# TrackerMini_V2.net
KiCad netlist of a schematic drawn in EAGLE
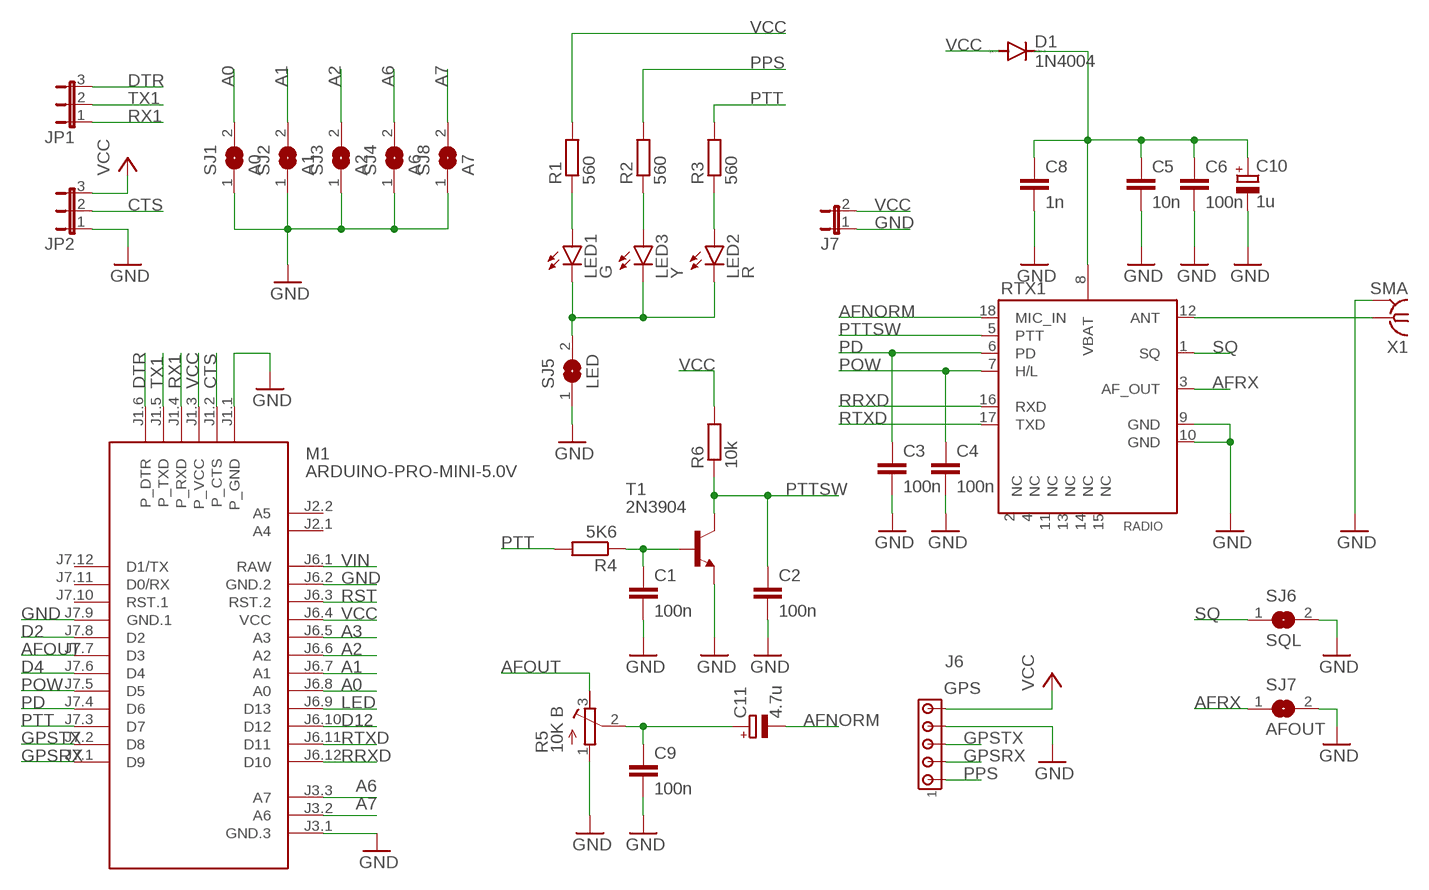
[diagram p0: schematic, sheet 1]

(export (version "E")
  (design (tool "Eeschema 10.0.6"))
  (components
    (comp (ref "C1")
      (value "100n")
      (footprint "eagle-import:C025-025X050")
      (libsource (lib "eagle-import") (part "C-EU025-025X050"))
    )
    (comp (ref "C2")
      (value "100n")
      (footprint "eagle-import:C025-025X050")
      (libsource (lib "eagle-import") (part "C-EU025-025X050"))
    )
    (comp (ref "C3")
      (value "100n")
      (footprint "eagle-import:C025-025X050")
      (libsource (lib "eagle-import") (part "C-EU025-025X050"))
    )
    (comp (ref "C4")
      (value "100n")
      (footprint "eagle-import:C025-025X050")
      (libsource (lib "eagle-import") (part "C-EU025-025X050"))
    )
    (comp (ref "C5")
      (value "10n")
      (footprint "eagle-import:C025-025X050")
      (libsource (lib "eagle-import") (part "C-EU025-025X050"))
    )
    (comp (ref "C6")
      (value "100n")
      (footprint "eagle-import:C025-025X050")
      (libsource (lib "eagle-import") (part "C-EU025-025X050"))
    )
    (comp (ref "C8")
      (value "1n")
      (footprint "eagle-import:C025-025X050")
      (libsource (lib "eagle-import") (part "C-EU025-025X050"))
    )
    (comp (ref "C9")
      (value "100n")
      (footprint "eagle-import:C025-025X050")
      (libsource (lib "eagle-import") (part "C-EU025-025X050"))
    )
    (comp (ref "C10")
      (value "1u")
      (footprint "eagle-import:E2-5")
      (libsource (lib "eagle-import") (part "CPOL-EUE2-5"))
    )
    (comp (ref "C11")
      (value "4.7u")
      (footprint "eagle-import:E2-5")
      (libsource (lib "eagle-import") (part "CPOL-EUE2-5"))
    )
    (comp (ref "D1")
      (value "1N4004")
      (footprint "eagle-import:DO41-10")
      (libsource (lib "eagle-import") (part "1N4004"))
    )
    (comp (ref "J6")
      (value "GPS")
      (footprint "eagle-import:10X05MTA")
      (libsource (lib "eagle-import") (part "MTA05-100"))
    )
    (comp (ref "J7")
      (value "JP1E")
      (footprint "eagle-import:JP1")
      (libsource (lib "eagle-import") (part "JP1E"))
    )
    (comp (ref "JP1")
      (value "JP2E")
      (footprint "eagle-import:JP2")
      (libsource (lib "eagle-import") (part "JP2E"))
    )
    (comp (ref "JP2")
      (value "JP2E")
      (footprint "eagle-import:JP2")
      (libsource (lib "eagle-import") (part "JP2E"))
    )
    (comp (ref "LED1")
      (value "G")
      (footprint "eagle-import:LED3MM")
      (fields (field (name "MF") "VISHAY SEMICONDUCTOR"))
      (libsource (lib "eagle-import") (part "TLLG4400"))
    )
    (comp (ref "LED2")
      (value "R")
      (footprint "eagle-import:LED3MM")
      (fields (field (name "MF") "VISHAY SEMICONDUCTOR"))
      (libsource (lib "eagle-import") (part "TLLR4400"))
    )
    (comp (ref "LED3")
      (value "Y")
      (footprint "eagle-import:LED3MM")
      (fields (field (name "MF") "VISHAY SEMICONDUCTOR"))
      (libsource (lib "eagle-import") (part "TLLY4400"))
    )
    (comp (ref "M1")
      (value "ARDUINO-PRO-MINI-5.0V")
      (footprint "eagle-import:ARDUINO-PRO-MINI")
      (libsource (lib "eagle-import") (part "ARDUINO-PRO-MINI-5.0V"))
    )
    (comp (ref "R1")
      (value "560")
      (footprint "eagle-import:0204_7")
      (libsource (lib "eagle-import") (part "R-EU_0204/7"))
    )
    (comp (ref "R2")
      (value "560")
      (footprint "eagle-import:0204_7")
      (libsource (lib "eagle-import") (part "R-EU_0204/7"))
    )
    (comp (ref "R3")
      (value "560")
      (footprint "eagle-import:0204_7")
      (libsource (lib "eagle-import") (part "R-EU_0204/7"))
    )
    (comp (ref "R4")
      (value "5K6")
      (footprint "eagle-import:0204_7")
      (libsource (lib "eagle-import") (part "R-EU_0204/7"))
    )
    (comp (ref "R5")
      (value "10K B")
      (footprint "eagle-import:RTRIM64W")
      (libsource (lib "eagle-import") (part "R-TRIMM64W"))
    )
    (comp (ref "R6")
      (value "10k")
      (footprint "eagle-import:0204_7")
      (libsource (lib "eagle-import") (part "R-EU_0204/7"))
    )
    (comp (ref "RTX1")
      (value "RADIO")
      (footprint "eagle-import:DRA818A")
      (libsource (lib "eagle-import") (part "DRA818A"))
    )
    (comp (ref "SJ1") (value "A0") (footprint "eagle-import:SJ") (libsource (lib "eagle-import") (part "SJ")))
    (comp (ref "SJ2") (value "A1") (footprint "eagle-import:SJ") (libsource (lib "eagle-import") (part "SJ")))
    (comp (ref "SJ3") (value "A2") (footprint "eagle-import:SJ") (libsource (lib "eagle-import") (part "SJ")))
    (comp (ref "SJ4") (value "A6") (footprint "eagle-import:SJ") (libsource (lib "eagle-import") (part "SJ")))
    (comp (ref "SJ5")
      (value "LED")
      (footprint "eagle-import:SJ")
      (libsource (lib "eagle-import") (part "SJ"))
    )
    (comp (ref "SJ6")
      (value "SQL")
      (footprint "eagle-import:SJW")
      (libsource (lib "eagle-import") (part "SJW"))
    )
    (comp (ref "SJ7")
      (value "AFOUT")
      (footprint "eagle-import:SJW")
      (libsource (lib "eagle-import") (part "SJW"))
    )
    (comp (ref "SJ8") (value "A7") (footprint "eagle-import:SJ") (libsource (lib "eagle-import") (part "SJ")))
    (comp (ref "T1")
      (value "2N3904")
      (footprint "eagle-import:TO92")
      (libsource (lib "eagle-import") (part "2N3904"))
    )
    (comp (ref "X1")
      (value "SMA")
      (footprint "eagle-import:J502-ND-142-0701-801_806")
      (fields (field (name "MF") "JOHNSON COMPONENTS") (field (name "MPN") "142-0701-801"))
      (libsource (lib "eagle-import") (part "SMA-142-0701-801/806"))
    )
  )
  (nets
    (net (code "1") (name "/A0") (class "Default")
      (node (ref "M1") (pin "J6.8") (pinfunction "A0_J6.8") (pintype "bidirectional"))
      (node (ref "SJ1") (pin "2") (pinfunction "2_2") (pintype "passive"))
    )
    (net (code "2") (name "/A1") (class "Default")
      (node (ref "M1") (pin "J6.7") (pinfunction "A1_J6.7") (pintype "bidirectional"))
      (node (ref "SJ2") (pin "2") (pinfunction "2_2") (pintype "passive"))
    )
    (net (code "3") (name "/A2") (class "Default")
      (node (ref "M1") (pin "J6.6") (pinfunction "A2_J6.6") (pintype "bidirectional"))
      (node (ref "SJ3") (pin "2") (pinfunction "2_2") (pintype "passive"))
    )
    (net (code "4") (name "/A3") (class "Default")
      (node (ref "M1") (pin "J6.5") (pinfunction "A3_J6.5") (pintype "bidirectional"))
    )
    (net (code "5") (name "/A6") (class "Default")
      (node (ref "M1") (pin "J3.3") (pinfunction "A7_J3.3") (pintype "bidirectional"))
      (node (ref "SJ4") (pin "2") (pinfunction "2_2") (pintype "passive"))
    )
    (net (code "6") (name "/A7") (class "Default")
      (node (ref "M1") (pin "J3.2") (pinfunction "A6_J3.2") (pintype "bidirectional"))
      (node (ref "SJ8") (pin "2") (pinfunction "2_2") (pintype "passive"))
    )
    (net (code "7") (name "/AFNORM") (class "Default")
      (node (ref "C11") (pin "-") (pinfunction "-_-") (pintype "passive"))
      (node (ref "RTX1") (pin "18") (pinfunction "MIC_IN_18") (pintype "bidirectional"))
    )
    (net (code "8") (name "/AFOUT") (class "Default")
      (node (ref "M1") (pin "J7.7") (pinfunction "D3_J7.7") (pintype "bidirectional"))
      (node (ref "R5") (pin "3") (pinfunction "E_3") (pintype "passive"))
    )
    (net (code "9") (name "/AFRX") (class "Default")
      (node (ref "RTX1") (pin "3") (pinfunction "AF_OUT_3") (pintype "bidirectional"))
      (node (ref "SJ7") (pin "1") (pinfunction "1_1") (pintype "passive"))
    )
    (net (code "10") (name "/CTS") (class "Default")
      (node (ref "JP2") (pin "2") (pinfunction "2_2") (pintype "passive"))
      (node (ref "M1") (pin "J1.2") (pinfunction "P_CTS_J1.2") (pintype "bidirectional"))
    )
    (net (code "11") (name "/D2") (class "Default")
      (node (ref "M1") (pin "J7.8") (pinfunction "D2_J7.8") (pintype "bidirectional"))
    )
    (net (code "12") (name "/D4") (class "Default")
      (node (ref "M1") (pin "J7.6") (pinfunction "D4_J7.6") (pintype "bidirectional"))
    )
    (net (code "13") (name "/D12") (class "Default")
      (node (ref "M1") (pin "J6.10") (pinfunction "D12_J6.10") (pintype "bidirectional"))
    )
    (net (code "14") (name "/DTR") (class "Default")
      (node (ref "JP1") (pin "3") (pinfunction "3_3") (pintype "passive"))
      (node (ref "M1") (pin "J1.6") (pinfunction "P_DTR_J1.6") (pintype "bidirectional"))
    )
    (net (code "15") (name "/GPSRX") (class "Default")
      (node (ref "J6") (pin "2") (pinfunction "2_2") (pintype "passive"))
      (node (ref "M1") (pin "J7.1") (pinfunction "D9_J7.1") (pintype "bidirectional"))
    )
    (net (code "16") (name "/GPSTX") (class "Default")
      (node (ref "J6") (pin "3") (pinfunction "3_3") (pintype "passive"))
      (node (ref "M1") (pin "J7.2") (pinfunction "D8_J7.2") (pintype "bidirectional"))
    )
    (net (code "17") (name "/LED") (class "Default")
      (node (ref "M1") (pin "J6.9") (pinfunction "D13_J6.9") (pintype "bidirectional"))
    )
    (net (code "18") (name "/PD") (class "Default")
      (node (ref "C3") (pin "1") (pinfunction "1_1") (pintype "passive"))
      (node (ref "M1") (pin "J7.4") (pinfunction "D6_J7.4") (pintype "bidirectional"))
      (node (ref "RTX1") (pin "6") (pinfunction "PD_6") (pintype "bidirectional"))
    )
    (net (code "19") (name "/POW") (class "Default")
      (node (ref "C4") (pin "1") (pinfunction "1_1") (pintype "passive"))
      (node (ref "M1") (pin "J7.5") (pinfunction "D5_J7.5") (pintype "bidirectional"))
      (node (ref "RTX1") (pin "7") (pinfunction "H/L_7") (pintype "bidirectional"))
    )
    (net (code "20") (name "/PPS") (class "Default")
      (node (ref "J6") (pin "1") (pinfunction "1_1") (pintype "passive"))
      (node (ref "R2") (pin "2") (pinfunction "2_2") (pintype "passive"))
    )
    (net (code "21") (name "/PTT") (class "Default")
      (node (ref "M1") (pin "J7.3") (pinfunction "D7_J7.3") (pintype "bidirectional"))
      (node (ref "R3") (pin "2") (pinfunction "2_2") (pintype "passive"))
      (node (ref "R4") (pin "2") (pinfunction "2_2") (pintype "passive"))
    )
    (net (code "22") (name "/PTTSW") (class "Default")
      (node (ref "C2") (pin "1") (pinfunction "1_1") (pintype "passive"))
      (node (ref "R6") (pin "1") (pinfunction "1_1") (pintype "passive"))
      (node (ref "RTX1") (pin "5") (pinfunction "PTT_5") (pintype "bidirectional"))
      (node (ref "T1") (pin "1") (pinfunction "C_1") (pintype "passive"))
    )
    (net (code "23") (name "/RRXD") (class "Default")
      (node (ref "M1") (pin "J6.12") (pinfunction "D10_J6.12") (pintype "bidirectional"))
      (node (ref "RTX1") (pin "16") (pinfunction "RXD_16") (pintype "bidirectional"))
    )
    (net (code "24") (name "/RST") (class "Default")
      (node (ref "M1") (pin "J6.3") (pinfunction "RST.2_J6.3") (pintype "bidirectional"))
    )
    (net (code "25") (name "/RTXD") (class "Default")
      (node (ref "M1") (pin "J6.11") (pinfunction "D11_J6.11") (pintype "bidirectional"))
      (node (ref "RTX1") (pin "17") (pinfunction "TXD_17") (pintype "bidirectional"))
    )
    (net (code "26") (name "/RX1") (class "Default")
      (node (ref "JP1") (pin "1") (pinfunction "1_1") (pintype "passive"))
      (node (ref "M1") (pin "J1.4") (pinfunction "P_RXD_J1.4") (pintype "bidirectional"))
    )
    (net (code "27") (name "/SQ") (class "Default")
      (node (ref "RTX1") (pin "1") (pinfunction "SQ_1") (pintype "bidirectional"))
      (node (ref "SJ6") (pin "1") (pinfunction "1_1") (pintype "passive"))
    )
    (net (code "28") (name "/TX1") (class "Default")
      (node (ref "JP1") (pin "2") (pinfunction "2_2") (pintype "passive"))
      (node (ref "M1") (pin "J1.5") (pinfunction "P_TXD_J1.5") (pintype "bidirectional"))
    )
    (net (code "29") (name "/VIN") (class "Default")
      (node (ref "M1") (pin "J6.1") (pinfunction "RAW_J6.1") (pintype "power_in"))
    )
    (net (code "30") (name "GND") (class "Default")
      (node (ref "C1") (pin "2") (pinfunction "2_2") (pintype "passive"))
      (node (ref "C10") (pin "-") (pinfunction "-_-") (pintype "passive"))
      (node (ref "C2") (pin "2") (pinfunction "2_2") (pintype "passive"))
      (node (ref "C3") (pin "2") (pinfunction "2_2") (pintype "passive"))
      (node (ref "C4") (pin "2") (pinfunction "2_2") (pintype "passive"))
      (node (ref "C5") (pin "2") (pinfunction "2_2") (pintype "passive"))
      (node (ref "C6") (pin "2") (pinfunction "2_2") (pintype "passive"))
      (node (ref "C8") (pin "2") (pinfunction "2_2") (pintype "passive"))
      (node (ref "C9") (pin "2") (pinfunction "2_2") (pintype "passive"))
      (node (ref "J6") (pin "4") (pinfunction "4_4") (pintype "passive"))
      (node (ref "J7") (pin "1") (pinfunction "1_1") (pintype "passive"))
      (node (ref "JP2") (pin "1") (pinfunction "1_1") (pintype "passive"))
      (node (ref "M1") (pin "J1.1") (pinfunction "P_GND_J1.1") (pintype "bidirectional"))
      (node (ref "M1") (pin "J3.1") (pinfunction "GND.3_J3.1") (pintype "bidirectional"))
      (node (ref "M1") (pin "J6.2") (pinfunction "GND.2_J6.2") (pintype "power_in"))
      (node (ref "M1") (pin "J7.9") (pinfunction "GND.1_J7.9") (pintype "power_in"))
      (node (ref "R5") (pin "1") (pinfunction "A_1") (pintype "passive"))
      (node (ref "RTX1") (pin "10") (pinfunction "GND_10") (pintype "bidirectional"))
      (node (ref "RTX1") (pin "9") (pinfunction "GND_9") (pintype "bidirectional"))
      (node (ref "SJ1") (pin "1") (pinfunction "1_1") (pintype "passive"))
      (node (ref "SJ2") (pin "1") (pinfunction "1_1") (pintype "passive"))
      (node (ref "SJ3") (pin "1") (pinfunction "1_1") (pintype "passive"))
      (node (ref "SJ4") (pin "1") (pinfunction "1_1") (pintype "passive"))
      (node (ref "SJ5") (pin "1") (pinfunction "1_1") (pintype "passive"))
      (node (ref "SJ6") (pin "2") (pinfunction "2_2") (pintype "passive"))
      (node (ref "SJ7") (pin "2") (pinfunction "2_2") (pintype "passive"))
      (node (ref "SJ8") (pin "1") (pinfunction "1_1") (pintype "passive"))
      (node (ref "T1") (pin "3") (pinfunction "E_3") (pintype "passive"))
      (node (ref "X1") (pin "G@1") (pinfunction "2_G@1") (pintype "passive"))
      (node (ref "X1") (pin "G@2") (pinfunction "2_G@2") (pintype "passive"))
      (node (ref "X1") (pin "G@3") (pinfunction "2_G@3") (pintype "passive"))
      (node (ref "X1") (pin "G@4") (pinfunction "2_G@4") (pintype "passive"))
    )
    (net (code "31") (name "Net-(LED1-C)") (class "Default")
      (node (ref "LED1") (pin "K") (pinfunction "C_K") (pintype "passive"))
      (node (ref "LED2") (pin "K") (pinfunction "C_K") (pintype "passive"))
      (node (ref "LED3") (pin "K") (pinfunction "C_K") (pintype "passive"))
      (node (ref "SJ5") (pin "2") (pinfunction "2_2") (pintype "passive"))
    )
    (net (code "32") (name "Net-(LED1-PadA)") (class "Default")
      (node (ref "LED1") (pin "A") (pinfunction "A_A") (pintype "passive"))
      (node (ref "R1") (pin "1") (pinfunction "1_1") (pintype "passive"))
    )
    (net (code "33") (name "Net-(LED2-PadA)") (class "Default")
      (node (ref "LED2") (pin "A") (pinfunction "A_A") (pintype "passive"))
      (node (ref "R3") (pin "1") (pinfunction "1_1") (pintype "passive"))
    )
    (net (code "34") (name "Net-(LED3-PadA)") (class "Default")
      (node (ref "LED3") (pin "A") (pinfunction "A_A") (pintype "passive"))
      (node (ref "R2") (pin "1") (pinfunction "1_1") (pintype "passive"))
    )
    (net (code "35") (name "Net-(R5-S)") (class "Default")
      (node (ref "C11") (pin "+") (pinfunction "+_+") (pintype "passive"))
      (node (ref "C9") (pin "1") (pinfunction "1_1") (pintype "passive"))
      (node (ref "R5") (pin "2") (pinfunction "S_2") (pintype "passive"))
    )
    (net (code "36") (name "Net-(RTX1-ANT)") (class "Default")
      (node (ref "RTX1") (pin "12") (pinfunction "ANT_12") (pintype "bidirectional"))
      (node (ref "X1") (pin "1") (pinfunction "1_1") (pintype "passive"))
    )
    (net (code "37") (name "Net-(RTX1-VBAT)") (class "Default")
      (node (ref "C10") (pin "+") (pinfunction "+_+") (pintype "passive"))
      (node (ref "C5") (pin "1") (pinfunction "1_1") (pintype "passive"))
      (node (ref "C6") (pin "1") (pinfunction "1_1") (pintype "passive"))
      (node (ref "C8") (pin "1") (pinfunction "1_1") (pintype "passive"))
      (node (ref "D1") (pin "C") (pinfunction "C_C") (pintype "passive"))
      (node (ref "RTX1") (pin "8") (pinfunction "VBAT_8") (pintype "bidirectional"))
    )
    (net (code "38") (name "Net-(T1-B)") (class "Default")
      (node (ref "C1") (pin "1") (pinfunction "1_1") (pintype "passive"))
      (node (ref "R4") (pin "1") (pinfunction "1_1") (pintype "passive"))
      (node (ref "T1") (pin "2") (pinfunction "B_2") (pintype "passive"))
    )
    (net (code "39") (name "VCC") (class "Default")
      (node (ref "D1") (pin "A") (pinfunction "A_A") (pintype "passive"))
      (node (ref "J6") (pin "5") (pinfunction "5_5") (pintype "passive"))
      (node (ref "J7") (pin "2") (pinfunction "2_2") (pintype "passive"))
      (node (ref "JP2") (pin "3") (pinfunction "3_3") (pintype "passive"))
      (node (ref "M1") (pin "J1.3") (pinfunction "P_VCC_J1.3") (pintype "bidirectional"))
      (node (ref "M1") (pin "J6.4") (pinfunction "VCC_J6.4") (pintype "power_in"))
      (node (ref "R1") (pin "2") (pinfunction "2_2") (pintype "passive"))
      (node (ref "R6") (pin "2") (pinfunction "2_2") (pintype "passive"))
    )
    (net (code "40") (name "unconnected-(M1-A4-PadJ2.1)") (class "Default")
      (node (ref "M1") (pin "J2.1") (pinfunction "A4_J2.1") (pintype "bidirectional"))
    )
    (net (code "41") (name "unconnected-(M1-A5-PadJ2.2)") (class "Default")
      (node (ref "M1") (pin "J2.2") (pinfunction "A5_J2.2") (pintype "bidirectional"))
    )
    (net (code "42") (name "unconnected-(M1-D0{slash}RX-PadJ7.11)") (class "Default")
      (node (ref "M1") (pin "J7.11") (pinfunction "D0/RX_J7.11") (pintype "bidirectional"))
    )
    (net (code "43") (name "unconnected-(M1-D1{slash}TX-PadJ7.12)") (class "Default")
      (node (ref "M1") (pin "J7.12") (pinfunction "D1/TX_J7.12") (pintype "bidirectional"))
    )
    (net (code "44") (name "unconnected-(M1-RST.1-PadJ7.10)") (class "Default")
      (node (ref "M1") (pin "J7.10") (pinfunction "RST.1_J7.10") (pintype "bidirectional"))
    )
    (net (code "45") (name "unconnected-(RTX1-NC-Pad2)") (class "Default")
      (node (ref "RTX1") (pin "2") (pinfunction "NC_2") (pintype "bidirectional"))
    )
    (net (code "46") (name "unconnected-(RTX1-NC-Pad4)") (class "Default")
      (node (ref "RTX1") (pin "4") (pinfunction "NC_4") (pintype "bidirectional"))
    )
    (net (code "47") (name "unconnected-(RTX1-NC-Pad11)") (class "Default")
      (node (ref "RTX1") (pin "11") (pinfunction "NC_11") (pintype "bidirectional"))
    )
    (net (code "48") (name "unconnected-(RTX1-NC-Pad13)") (class "Default")
      (node (ref "RTX1") (pin "13") (pinfunction "NC_13") (pintype "bidirectional"))
    )
    (net (code "49") (name "unconnected-(RTX1-NC-Pad14)") (class "Default")
      (node (ref "RTX1") (pin "14") (pinfunction "NC_14") (pintype "bidirectional"))
    )
    (net (code "50") (name "unconnected-(RTX1-NC-Pad15)") (class "Default")
      (node (ref "RTX1") (pin "15") (pinfunction "NC_15") (pintype "bidirectional"))
    )
  )
)
